# 516_outin_arduino.net
KiCad netlist of a schematic drawn in EAGLE
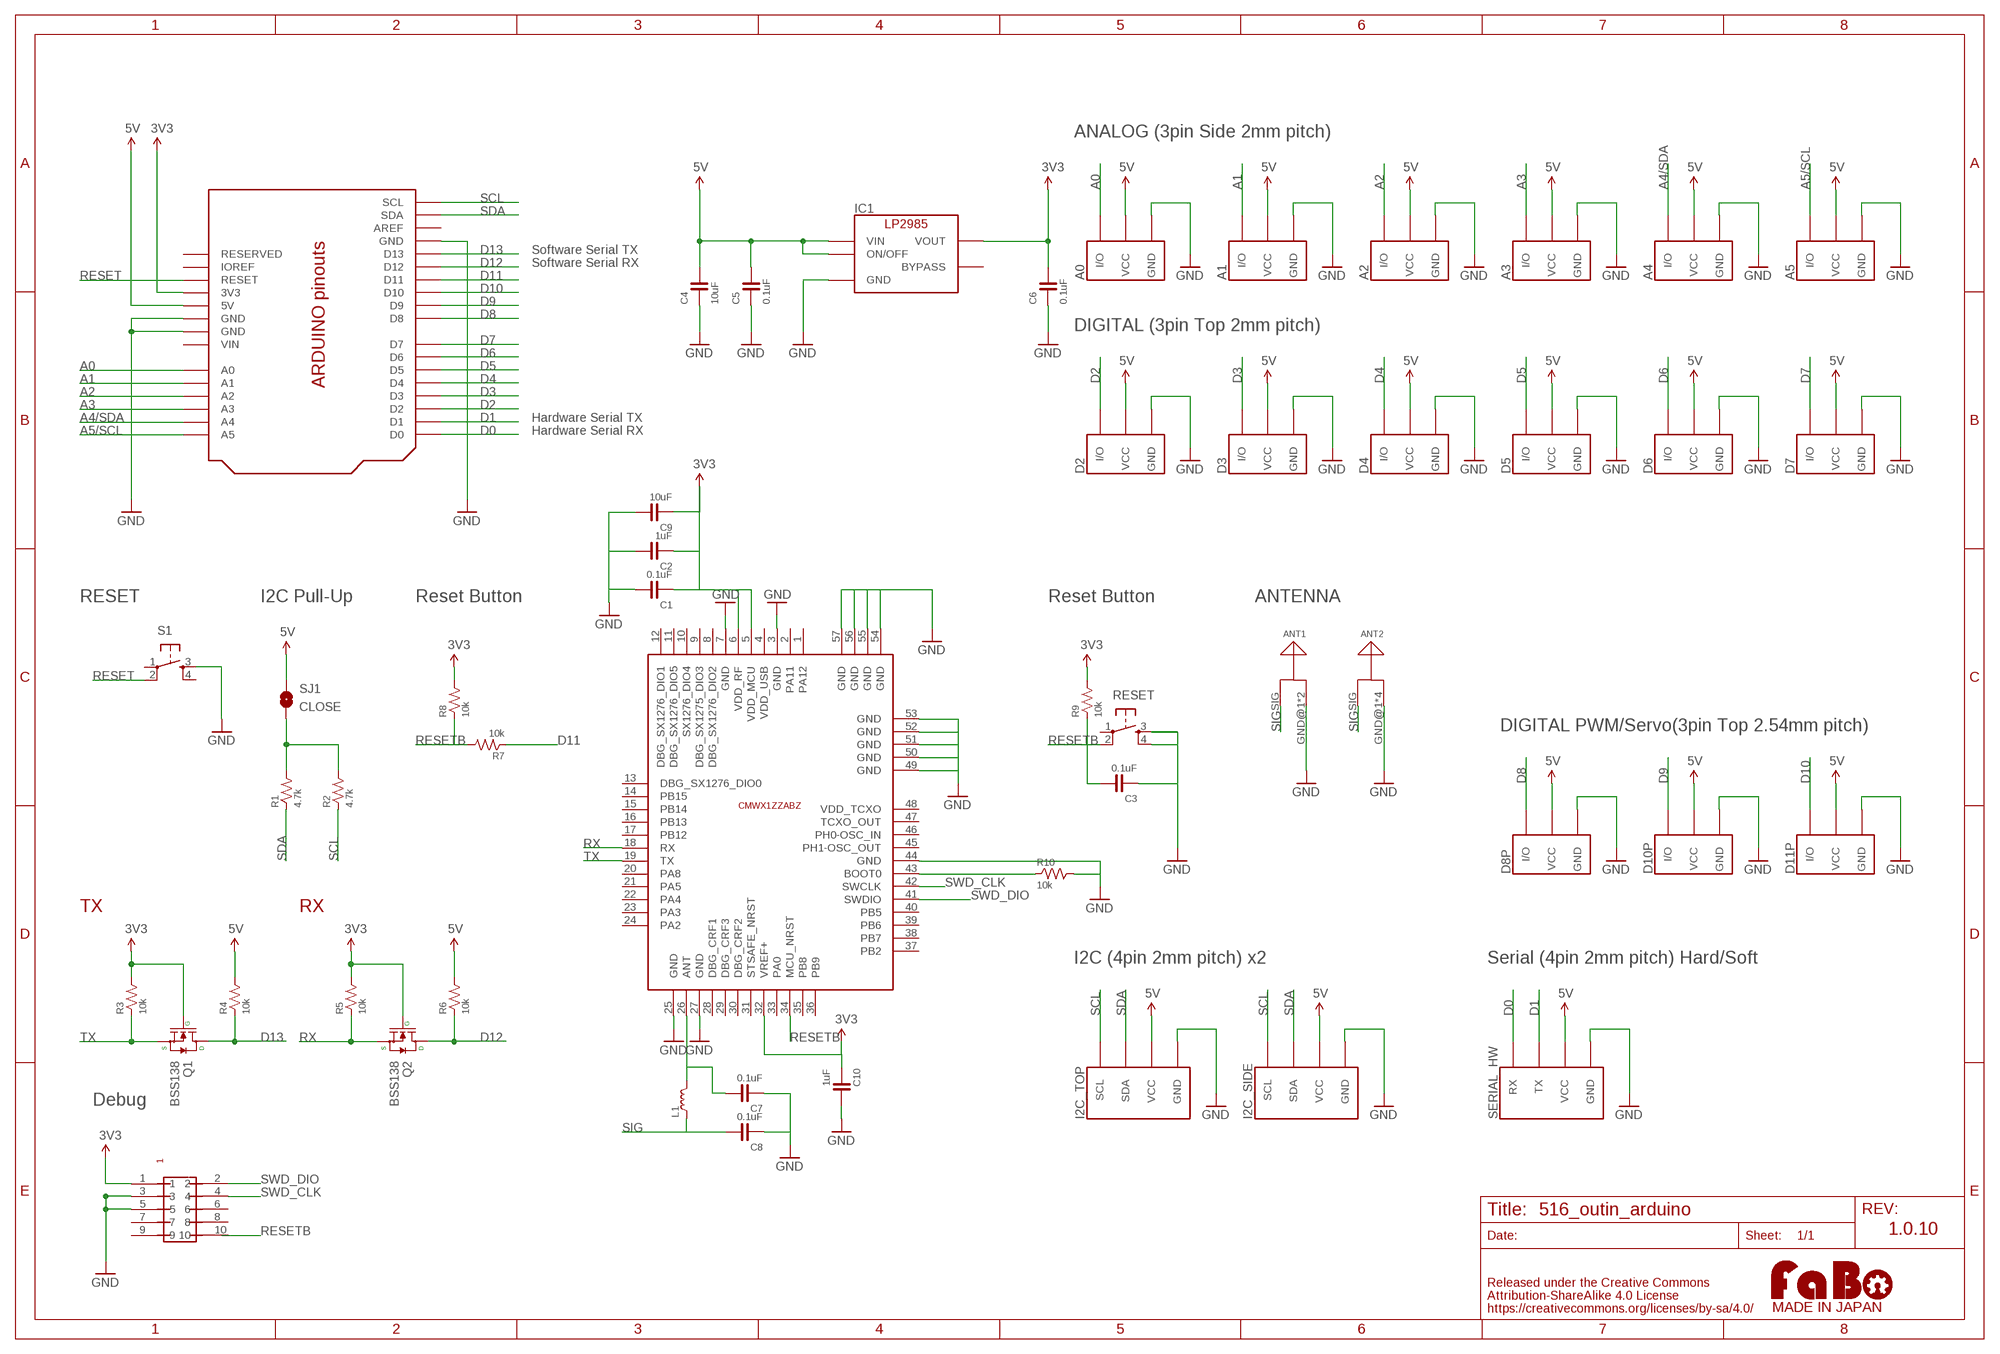
[diagram p0: schematic, sheet 1]

(export (version "E")
  (design (tool "Eeschema 10.0.6"))
  (components
    (comp (ref "A0")
      (value "FABO_BRICK_3PIN-S03B-PASK-2_LONG")
      (footprint "eagle-import:FABO_BRICK_3PIN_S03B-PASK-2_LONG")
      (libsource (lib "eagle-import") (part "FABO_BRICK_3PIN-S03B-PASK-2_LONG"))
    )
    (comp (ref "A1")
      (value "FABO_BRICK_3PIN-S03B-PASK-2_LONG")
      (footprint "eagle-import:FABO_BRICK_3PIN_S03B-PASK-2_LONG")
      (libsource (lib "eagle-import") (part "FABO_BRICK_3PIN-S03B-PASK-2_LONG"))
    )
    (comp (ref "A2")
      (value "FABO_BRICK_3PIN-S03B-PASK-2_LONG")
      (footprint "eagle-import:FABO_BRICK_3PIN_S03B-PASK-2_LONG")
      (libsource (lib "eagle-import") (part "FABO_BRICK_3PIN-S03B-PASK-2_LONG"))
    )
    (comp (ref "A3")
      (value "FABO_BRICK_3PIN-S03B-PASK-2_LONG")
      (footprint "eagle-import:FABO_BRICK_3PIN_S03B-PASK-2_LONG")
      (libsource (lib "eagle-import") (part "FABO_BRICK_3PIN-S03B-PASK-2_LONG"))
    )
    (comp (ref "A4")
      (value "FABO_BRICK_3PIN-S03B-PASK-2_LONG")
      (footprint "eagle-import:FABO_BRICK_3PIN_S03B-PASK-2_LONG")
      (libsource (lib "eagle-import") (part "FABO_BRICK_3PIN-S03B-PASK-2_LONG"))
    )
    (comp (ref "A5")
      (value "FABO_BRICK_3PIN-S03B-PASK-2_LONG")
      (footprint "eagle-import:FABO_BRICK_3PIN_S03B-PASK-2_LONG")
      (libsource (lib "eagle-import") (part "FABO_BRICK_3PIN-S03B-PASK-2_LONG"))
    )
    (comp (ref "ANT1")
      (value "ANTENA_HIROSE-UF-L")
      (footprint "eagle-import:HIROSE-UF-L")
      (libsource (lib "eagle-import") (part "ANTENA_HIROSE-UF-L"))
    )
    (comp (ref "ANT2")
      (value "ANTENA_SMA-J-P-H-RA-TH1")
      (footprint "eagle-import:SMA–J–P–H–RA–TH1")
      (libsource (lib "eagle-import") (part "ANTENA_SMA-J-P-H-RA-TH1"))
    )
    (comp (ref "C1")
      (value "0.1uF")
      (footprint "eagle-import:0603-NARROW")
      (libsource (lib "eagle-import") (part "CAPACITOR-0603_NARROW"))
    )
    (comp (ref "C2")
      (value "1uF")
      (footprint "eagle-import:0603-NARROW")
      (libsource (lib "eagle-import") (part "CAPACITOR-0603_NARROW"))
    )
    (comp (ref "C3")
      (value "0.1uF")
      (footprint "eagle-import:0603-NARROW")
      (libsource (lib "eagle-import") (part "CAPACITOR-0603_NARROW"))
    )
    (comp (ref "C4")
      (value "10uF")
      (footprint "eagle-import:0603-NARROW")
      (libsource (lib "eagle-import") (part "CAPACITOR-0603_NARROW"))
    )
    (comp (ref "C5")
      (value "0.1uF")
      (footprint "eagle-import:0603-NARROW")
      (libsource (lib "eagle-import") (part "CAPACITOR-0603_NARROW"))
    )
    (comp (ref "C6")
      (value "0.1uF")
      (footprint "eagle-import:0603-NARROW")
      (libsource (lib "eagle-import") (part "CAPACITOR-0603_NARROW"))
    )
    (comp (ref "C7")
      (value "0.1uF")
      (footprint "eagle-import:0603-NARROW")
      (libsource (lib "eagle-import") (part "CAPACITOR-0603_NARROW"))
    )
    (comp (ref "C8")
      (value "0.1uF")
      (footprint "eagle-import:0603-NARROW")
      (libsource (lib "eagle-import") (part "CAPACITOR-0603_NARROW"))
    )
    (comp (ref "C9")
      (value "10uF")
      (footprint "eagle-import:0603-NARROW")
      (libsource (lib "eagle-import") (part "CAPACITOR-0603_NARROW"))
    )
    (comp (ref "C10")
      (value "1uF")
      (footprint "eagle-import:0603-NARROW")
      (libsource (lib "eagle-import") (part "CAPACITOR-0603_NARROW"))
    )
    (comp (ref "D2")
      (value "FABO_BRICK_3PIN-B03B-PASK-1")
      (footprint "eagle-import:FABO_BRICK_3PIN_B03B-PASK-1")
      (libsource (lib "eagle-import") (part "FABO_BRICK_3PIN-B03B-PASK-1"))
    )
    (comp (ref "D3")
      (value "FABO_BRICK_3PIN-B03B-PASK-1")
      (footprint "eagle-import:FABO_BRICK_3PIN_B03B-PASK-1")
      (libsource (lib "eagle-import") (part "FABO_BRICK_3PIN-B03B-PASK-1"))
    )
    (comp (ref "D4")
      (value "FABO_BRICK_3PIN-B03B-PASK-1")
      (footprint "eagle-import:FABO_BRICK_3PIN_B03B-PASK-1")
      (libsource (lib "eagle-import") (part "FABO_BRICK_3PIN-B03B-PASK-1"))
    )
    (comp (ref "D5")
      (value "FABO_BRICK_3PIN-B03B-PASK-1")
      (footprint "eagle-import:FABO_BRICK_3PIN_B03B-PASK-1")
      (libsource (lib "eagle-import") (part "FABO_BRICK_3PIN-B03B-PASK-1"))
    )
    (comp (ref "D6")
      (value "FABO_BRICK_3PIN-B03B-PASK-1")
      (footprint "eagle-import:FABO_BRICK_3PIN_B03B-PASK-1")
      (libsource (lib "eagle-import") (part "FABO_BRICK_3PIN-B03B-PASK-1"))
    )
    (comp (ref "D7")
      (value "FABO_BRICK_3PIN-B03B-PASK-1")
      (footprint "eagle-import:FABO_BRICK_3PIN_B03B-PASK-1")
      (libsource (lib "eagle-import") (part "FABO_BRICK_3PIN-B03B-PASK-1"))
    )
    (comp (ref "D8P")
      (value "FABO_BRICK_3PIN-HEADER")
      (footprint "eagle-import:FABO_BRICK_3PIN_HEADER")
      (libsource (lib "eagle-import") (part "FABO_BRICK_3PIN-HEADER"))
    )
    (comp (ref "D10P")
      (value "FABO_BRICK_3PIN-HEADER")
      (footprint "eagle-import:FABO_BRICK_3PIN_HEADER")
      (libsource (lib "eagle-import") (part "FABO_BRICK_3PIN-HEADER"))
    )
    (comp (ref "D11P")
      (value "FABO_BRICK_3PIN-HEADER")
      (footprint "eagle-import:FABO_BRICK_3PIN_HEADER")
      (libsource (lib "eagle-import") (part "FABO_BRICK_3PIN-HEADER"))
    )
    (comp (ref "I2C_SIDE")
      (value "FABO_BRICK_I2C-S04B-PASK-2_LONG")
      (footprint "eagle-import:FABO_BRICK_I2C_S04B-PASK-2_LONG")
      (libsource (lib "eagle-import") (part "FABO_BRICK_I2C-S04B-PASK-2_LONG"))
    )
    (comp (ref "I2C_TOP")
      (value "FABO_BRICK_I2C-B04B-PASK-1")
      (footprint "eagle-import:FABO_BRICK_I2C_B04B-PASK-1")
      (libsource (lib "eagle-import") (part "FABO_BRICK_I2C-B04B-PASK-1"))
    )
    (comp (ref "IC1")
      (value "LP2985-33DBV")
      (footprint "eagle-import:SOT-23-5")
      (libsource (lib "eagle-import") (part "LP2985-33DBV"))
    )
    (comp (ref "L1")
      (value "COIL-0603")
      (footprint "eagle-import:0603")
      (libsource (lib "eagle-import") (part "COIL-0603"))
    )
    (comp (ref "Q1")
      (value "BSS138")
      (footprint "eagle-import:SOT23-3")
      (libsource (lib "eagle-import") (part "MOSFET-N"))
    )
    (comp (ref "Q2")
      (value "BSS138")
      (footprint "eagle-import:SOT23-3")
      (libsource (lib "eagle-import") (part "MOSFET-N"))
    )
    (comp (ref "R1")
      (value "4.7k")
      (footprint "eagle-import:0603")
      (libsource (lib "eagle-import") (part "RESISTOR-0603"))
    )
    (comp (ref "R2")
      (value "4.7k")
      (footprint "eagle-import:0603")
      (libsource (lib "eagle-import") (part "RESISTOR-0603"))
    )
    (comp (ref "R3")
      (value "10k")
      (footprint "eagle-import:0603-NARROW")
      (libsource (lib "eagle-import") (part "RESISTOR-0603-NARROW"))
    )
    (comp (ref "R4")
      (value "10k")
      (footprint "eagle-import:0603-NARROW")
      (libsource (lib "eagle-import") (part "RESISTOR-0603-NARROW"))
    )
    (comp (ref "R5")
      (value "10k")
      (footprint "eagle-import:0603-NARROW")
      (libsource (lib "eagle-import") (part "RESISTOR-0603-NARROW"))
    )
    (comp (ref "R6")
      (value "10k")
      (footprint "eagle-import:0603-NARROW")
      (libsource (lib "eagle-import") (part "RESISTOR-0603-NARROW"))
    )
    (comp (ref "R7")
      (value "10k")
      (footprint "eagle-import:0603-NARROW")
      (libsource (lib "eagle-import") (part "RESISTOR-0603-NARROW"))
    )
    (comp (ref "R8")
      (value "10k")
      (footprint "eagle-import:0603-NARROW")
      (libsource (lib "eagle-import") (part "RESISTOR-0603-NARROW"))
    )
    (comp (ref "R9")
      (value "10k")
      (footprint "eagle-import:0603-NARROW")
      (libsource (lib "eagle-import") (part "RESISTOR-0603-NARROW"))
    )
    (comp (ref "R10")
      (value "10k")
      (footprint "eagle-import:0603-NARROW")
      (libsource (lib "eagle-import") (part "RESISTOR-0603-NARROW"))
    )
    (comp (ref "RESET")
      (value "TACT-SWITCH-SMD_KMR2")
      (footprint "eagle-import:KMR2")
      (libsource (lib "eagle-import") (part "TACT-SWITCH-SMD_KMR2"))
    )
    (comp (ref "S1")
      (value "TACT-SWITCH-6MM")
      (footprint "eagle-import:DTS_6_V")
      (libsource (lib "eagle-import") (part "TACT-SWITCH-6MM"))
    )
    (comp (ref "SERIAL_HW")
      (value "FABO_BRICK_SERIAL-B04B-PASK-1")
      (footprint "eagle-import:FABO_BRICK_SERIAL_B04B-PASK-1")
      (libsource (lib "eagle-import") (part "FABO_BRICK_SERIAL-B04B-PASK-1"))
    )
    (comp (ref "SJ1")
      (value "CLOSE")
      (footprint "eagle-import:SMD-JUMPER-2-CLOSE")
      (libsource (lib "eagle-import") (part "SMD-JUMPER-2-CLOSE"))
    )
    (comp (ref "U$3")
      (value "CMWX1ZZABZ")
      (footprint "eagle-import:CMWX1ZZABZ")
      (libsource (lib "eagle-import") (part "CMWX1ZZABZ"))
    )
    (comp (ref "U$10")
      (value "LOGO_FABO-M")
      (footprint "eagle-import:LOGO_FABO_MS")
      (libsource (lib "eagle-import") (part "LOGO_FABO-M"))
    )
    (comp (ref "U$15")
      (value "PIN-HEADER-SMT(1.27MM)2X5")
      (footprint "eagle-import:PIN-HEADER-SMT(1.27MM)2X5")
      (libsource (lib "eagle-import") (part "PIN-HEADER-SMT(1.27MM)2X5"))
    )
    (comp (ref "U1")
      (value "ARDUINO_UNO_R3_SHIELD-OUTIN")
      (footprint "eagle-import:ARDUINO_SHIELD_OUTIN")
      (libsource (lib "eagle-import") (part "ARDUINO_UNO_R3_SHIELD-OUTIN"))
    )
  )
  (nets
    (net (code "1") (name "/A0") (class "Default")
      (node (ref "A0") (pin "I/O") (pinfunction "I/O_I/O") (pintype "bidirectional"))
      (node (ref "U1") (pin "A0") (pinfunction "A0_A0") (pintype "bidirectional"))
    )
    (net (code "2") (name "/A1") (class "Default")
      (node (ref "A1") (pin "I/O") (pinfunction "I/O_I/O") (pintype "bidirectional"))
      (node (ref "U1") (pin "A1") (pinfunction "A1_A1") (pintype "bidirectional"))
    )
    (net (code "3") (name "/A2") (class "Default")
      (node (ref "A2") (pin "I/O") (pinfunction "I/O_I/O") (pintype "bidirectional"))
      (node (ref "U1") (pin "A2") (pinfunction "A2_A2") (pintype "bidirectional"))
    )
    (net (code "4") (name "/A3") (class "Default")
      (node (ref "A3") (pin "I/O") (pinfunction "I/O_I/O") (pintype "bidirectional"))
      (node (ref "U1") (pin "A3") (pinfunction "A3_A3") (pintype "bidirectional"))
    )
    (net (code "5") (name "/A4{slash}SDA") (class "Default")
      (node (ref "A4") (pin "I/O") (pinfunction "I/O_I/O") (pintype "bidirectional"))
      (node (ref "U1") (pin "A4") (pinfunction "A4_A4") (pintype "bidirectional"))
    )
    (net (code "6") (name "/A5{slash}SCL") (class "Default")
      (node (ref "A5") (pin "I/O") (pinfunction "I/O_I/O") (pintype "bidirectional"))
      (node (ref "U1") (pin "A5") (pinfunction "A5_A5") (pintype "bidirectional"))
    )
    (net (code "7") (name "/D0") (class "Default")
      (node (ref "SERIAL_HW") (pin "RX") (pinfunction "RX_RX") (pintype "bidirectional"))
      (node (ref "U1") (pin "D0") (pinfunction "D0_D0") (pintype "bidirectional"))
    )
    (net (code "8") (name "/D1") (class "Default")
      (node (ref "SERIAL_HW") (pin "TX") (pinfunction "TX_TX") (pintype "bidirectional"))
      (node (ref "U1") (pin "D1") (pinfunction "D1_D1") (pintype "bidirectional"))
    )
    (net (code "9") (name "/D2") (class "Default")
      (node (ref "D2") (pin "I/O") (pinfunction "I/O_I/O") (pintype "bidirectional"))
      (node (ref "U1") (pin "D2") (pinfunction "D2_D2") (pintype "bidirectional"))
    )
    (net (code "10") (name "/D3") (class "Default")
      (node (ref "D3") (pin "I/O") (pinfunction "I/O_I/O") (pintype "bidirectional"))
      (node (ref "U1") (pin "D3") (pinfunction "D3_D3") (pintype "bidirectional"))
    )
    (net (code "11") (name "/D4") (class "Default")
      (node (ref "D4") (pin "I/O") (pinfunction "I/O_I/O") (pintype "bidirectional"))
      (node (ref "U1") (pin "D4") (pinfunction "D4_D4") (pintype "bidirectional"))
    )
    (net (code "12") (name "/D5") (class "Default")
      (node (ref "D5") (pin "I/O") (pinfunction "I/O_I/O") (pintype "bidirectional"))
      (node (ref "U1") (pin "D5") (pinfunction "D5_D5") (pintype "bidirectional"))
    )
    (net (code "13") (name "/D6") (class "Default")
      (node (ref "D6") (pin "I/O") (pinfunction "I/O_I/O") (pintype "bidirectional"))
      (node (ref "U1") (pin "D6") (pinfunction "D6_D6") (pintype "bidirectional"))
    )
    (net (code "14") (name "/D7") (class "Default")
      (node (ref "D7") (pin "I/O") (pinfunction "I/O_I/O") (pintype "bidirectional"))
      (node (ref "U1") (pin "D7") (pinfunction "D7_D7") (pintype "bidirectional"))
    )
    (net (code "15") (name "/D8") (class "Default")
      (node (ref "D8P") (pin "I/O") (pinfunction "I/O_I/O") (pintype "bidirectional"))
      (node (ref "U1") (pin "D8") (pinfunction "D8_D8") (pintype "bidirectional"))
    )
    (net (code "16") (name "/D9") (class "Default")
      (node (ref "D10P") (pin "I/O") (pinfunction "I/O_I/O") (pintype "bidirectional"))
      (node (ref "U1") (pin "D9") (pinfunction "D9_D9") (pintype "bidirectional"))
    )
    (net (code "17") (name "/D10") (class "Default")
      (node (ref "D11P") (pin "I/O") (pinfunction "I/O_I/O") (pintype "bidirectional"))
      (node (ref "U1") (pin "D10") (pinfunction "D10_D10") (pintype "bidirectional"))
    )
    (net (code "18") (name "/D11") (class "Default")
      (node (ref "R7") (pin "1") (pinfunction "1_1") (pintype "bidirectional"))
      (node (ref "U1") (pin "D11") (pinfunction "D11_D11") (pintype "bidirectional"))
    )
    (net (code "19") (name "/D12") (class "Default")
      (node (ref "Q2") (pin "3") (pinfunction "D_3") (pintype "passive"))
      (node (ref "R6") (pin "1") (pinfunction "1_1") (pintype "bidirectional"))
      (node (ref "U1") (pin "D12") (pinfunction "D12_D12") (pintype "bidirectional"))
    )
    (net (code "20") (name "/D13") (class "Default")
      (node (ref "Q1") (pin "3") (pinfunction "D_3") (pintype "passive"))
      (node (ref "R4") (pin "1") (pinfunction "1_1") (pintype "bidirectional"))
      (node (ref "U1") (pin "D13") (pinfunction "D13_D13") (pintype "bidirectional"))
    )
    (net (code "21") (name "/RESET") (class "Default")
      (node (ref "S1") (pin "2") (pinfunction "2_2") (pintype "passive"))
      (node (ref "U1") (pin "RESET") (pinfunction "RESET_RESET") (pintype "bidirectional"))
    )
    (net (code "22") (name "/RESETB") (class "Default")
      (node (ref "C3") (pin "2") (pinfunction "2_2") (pintype "passive"))
      (node (ref "R7") (pin "2") (pinfunction "2_2") (pintype "bidirectional"))
      (node (ref "R8") (pin "1") (pinfunction "1_1") (pintype "bidirectional"))
      (node (ref "R9") (pin "1") (pinfunction "1_1") (pintype "bidirectional"))
      (node (ref "RESET") (pin "2") (pinfunction "2_2") (pintype "passive"))
      (node (ref "U$15") (pin "10") (pinfunction "10_10") (pintype "bidirectional"))
      (node (ref "U$3") (pin "34") (pinfunction "MCU_NRST_34") (pintype "bidirectional"))
    )
    (net (code "23") (name "/RX") (class "Default")
      (node (ref "Q2") (pin "2") (pinfunction "S_2") (pintype "passive"))
      (node (ref "R5") (pin "1") (pinfunction "1_1") (pintype "bidirectional"))
      (node (ref "U$3") (pin "18") (pinfunction "RX_18") (pintype "bidirectional"))
    )
    (net (code "24") (name "/SCL") (class "Default")
      (node (ref "I2C_SIDE") (pin "SCL") (pinfunction "SCL_SCL") (pintype "bidirectional"))
      (node (ref "I2C_TOP") (pin "SCL") (pinfunction "SCL_SCL") (pintype "bidirectional"))
      (node (ref "R2") (pin "1") (pinfunction "1_1") (pintype "bidirectional"))
      (node (ref "U1") (pin "SCL") (pinfunction "SCL_SCL") (pintype "bidirectional"))
    )
    (net (code "25") (name "/SDA") (class "Default")
      (node (ref "I2C_SIDE") (pin "SDA") (pinfunction "SDA_SDA") (pintype "bidirectional"))
      (node (ref "I2C_TOP") (pin "SDA") (pinfunction "SDA_SDA") (pintype "bidirectional"))
      (node (ref "R1") (pin "1") (pinfunction "1_1") (pintype "bidirectional"))
      (node (ref "U1") (pin "SDA") (pinfunction "SDA_SDA") (pintype "bidirectional"))
    )
    (net (code "26") (name "/SIG") (class "Default")
      (node (ref "ANT1") (pin "SIG") (pinfunction "SIG_SIG") (pintype "passive"))
      (node (ref "ANT2") (pin "SIG") (pinfunction "SIG_SIG") (pintype "passive"))
      (node (ref "C8") (pin "2") (pinfunction "2_2") (pintype "passive"))
      (node (ref "L1") (pin "1") (pinfunction "1_1") (pintype "bidirectional"))
    )
    (net (code "27") (name "/SWD_CLK") (class "Default")
      (node (ref "U$15") (pin "4") (pinfunction "4_4") (pintype "bidirectional"))
      (node (ref "U$3") (pin "42") (pinfunction "SWCLK_42") (pintype "bidirectional"))
    )
    (net (code "28") (name "/SWD_DIO") (class "Default")
      (node (ref "U$15") (pin "2") (pinfunction "2_2") (pintype "bidirectional"))
      (node (ref "U$3") (pin "41") (pinfunction "SWDIO_41") (pintype "bidirectional"))
    )
    (net (code "29") (name "/TX") (class "Default")
      (node (ref "Q1") (pin "2") (pinfunction "S_2") (pintype "passive"))
      (node (ref "R3") (pin "1") (pinfunction "1_1") (pintype "bidirectional"))
      (node (ref "U$3") (pin "19") (pinfunction "TX_19") (pintype "bidirectional"))
    )
    (net (code "30") (name "/VIN") (class "Default")
      (node (ref "U1") (pin "VIN") (pinfunction "VIN_VIN") (pintype "power_in"))
    )
    (net (code "31") (name "3V3") (class "Default")
      (node (ref "C1") (pin "1") (pinfunction "1_1") (pintype "passive"))
      (node (ref "C10") (pin "1") (pinfunction "1_1") (pintype "passive"))
      (node (ref "C2") (pin "1") (pinfunction "1_1") (pintype "passive"))
      (node (ref "C6") (pin "2") (pinfunction "2_2") (pintype "passive"))
      (node (ref "C9") (pin "1") (pinfunction "1_1") (pintype "passive"))
      (node (ref "IC1") (pin "5") (pinfunction "VOUT_5") (pintype "output"))
      (node (ref "Q1") (pin "1") (pinfunction "G_1") (pintype "passive"))
      (node (ref "Q2") (pin "1") (pinfunction "G_1") (pintype "passive"))
      (node (ref "R3") (pin "2") (pinfunction "2_2") (pintype "bidirectional"))
      (node (ref "R5") (pin "2") (pinfunction "2_2") (pintype "bidirectional"))
      (node (ref "R8") (pin "2") (pinfunction "2_2") (pintype "bidirectional"))
      (node (ref "R9") (pin "2") (pinfunction "2_2") (pintype "bidirectional"))
      (node (ref "U$15") (pin "1") (pinfunction "1_1") (pintype "bidirectional"))
      (node (ref "U$3") (pin "32") (pinfunction "VREF+_32") (pintype "bidirectional"))
      (node (ref "U$3") (pin "5") (pinfunction "VDD_MCU_5") (pintype "bidirectional"))
      (node (ref "U$3") (pin "6") (pinfunction "VDD_RF_6") (pintype "bidirectional"))
      (node (ref "U1") (pin "3V3") (pinfunction "3V3_3V3") (pintype "power_in"))
    )
    (net (code "32") (name "5V") (class "Default")
      (node (ref "A0") (pin "VCC") (pinfunction "VCC_VCC") (pintype "bidirectional"))
      (node (ref "A1") (pin "VCC") (pinfunction "VCC_VCC") (pintype "bidirectional"))
      (node (ref "A2") (pin "VCC") (pinfunction "VCC_VCC") (pintype "bidirectional"))
      (node (ref "A3") (pin "VCC") (pinfunction "VCC_VCC") (pintype "bidirectional"))
      (node (ref "A4") (pin "VCC") (pinfunction "VCC_VCC") (pintype "bidirectional"))
      (node (ref "A5") (pin "VCC") (pinfunction "VCC_VCC") (pintype "bidirectional"))
      (node (ref "C4") (pin "2") (pinfunction "2_2") (pintype "passive"))
      (node (ref "C5") (pin "2") (pinfunction "2_2") (pintype "passive"))
      (node (ref "D10P") (pin "VCC") (pinfunction "VCC_VCC") (pintype "bidirectional"))
      (node (ref "D11P") (pin "VCC") (pinfunction "VCC_VCC") (pintype "bidirectional"))
      (node (ref "D2") (pin "VCC") (pinfunction "VCC_VCC") (pintype "bidirectional"))
      (node (ref "D3") (pin "VCC") (pinfunction "VCC_VCC") (pintype "bidirectional"))
      (node (ref "D4") (pin "VCC") (pinfunction "VCC_VCC") (pintype "bidirectional"))
      (node (ref "D5") (pin "VCC") (pinfunction "VCC_VCC") (pintype "bidirectional"))
      (node (ref "D6") (pin "VCC") (pinfunction "VCC_VCC") (pintype "bidirectional"))
      (node (ref "D7") (pin "VCC") (pinfunction "VCC_VCC") (pintype "bidirectional"))
      (node (ref "D8P") (pin "VCC") (pinfunction "VCC_VCC") (pintype "bidirectional"))
      (node (ref "I2C_SIDE") (pin "VCC") (pinfunction "VCC_VCC") (pintype "bidirectional"))
      (node (ref "I2C_TOP") (pin "VCC") (pinfunction "VCC_VCC") (pintype "bidirectional"))
      (node (ref "IC1") (pin "1") (pinfunction "VIN_1") (pintype "input"))
      (node (ref "IC1") (pin "3") (pinfunction "ON/OFF_3") (pintype "input"))
      (node (ref "R4") (pin "2") (pinfunction "2_2") (pintype "bidirectional"))
      (node (ref "R6") (pin "2") (pinfunction "2_2") (pintype "bidirectional"))
      (node (ref "SERIAL_HW") (pin "VCC") (pinfunction "VCC_VCC") (pintype "bidirectional"))
      (node (ref "SJ1") (pin "1") (pinfunction "1_1") (pintype "passive"))
      (node (ref "U1") (pin "5V") (pinfunction "5V_5V") (pintype "power_in"))
    )
    (net (code "33") (name "GND") (class "Default")
      (node (ref "A0") (pin "GND") (pinfunction "GND_GND") (pintype "bidirectional"))
      (node (ref "A1") (pin "GND") (pinfunction "GND_GND") (pintype "bidirectional"))
      (node (ref "A2") (pin "GND") (pinfunction "GND_GND") (pintype "bidirectional"))
      (node (ref "A3") (pin "GND") (pinfunction "GND_GND") (pintype "bidirectional"))
      (node (ref "A4") (pin "GND") (pinfunction "GND_GND") (pintype "bidirectional"))
      (node (ref "A5") (pin "GND") (pinfunction "GND_GND") (pintype "bidirectional"))
      (node (ref "ANT1") (pin "GND@1") (pinfunction "GND_GND@1") (pintype "passive"))
      (node (ref "ANT1") (pin "GND@2") (pinfunction "GND_GND@2") (pintype "passive"))
      (node (ref "ANT2") (pin "GND@1") (pinfunction "GND_GND@1") (pintype "passive"))
      (node (ref "ANT2") (pin "GND@2") (pinfunction "GND_GND@2") (pintype "passive"))
      (node (ref "ANT2") (pin "GND@3") (pinfunction "GND_GND@3") (pintype "passive"))
      (node (ref "ANT2") (pin "GND@4") (pinfunction "GND_GND@4") (pintype "passive"))
      (node (ref "C1") (pin "2") (pinfunction "2_2") (pintype "passive"))
      (node (ref "C10") (pin "2") (pinfunction "2_2") (pintype "passive"))
      (node (ref "C2") (pin "2") (pinfunction "2_2") (pintype "passive"))
      (node (ref "C3") (pin "1") (pinfunction "1_1") (pintype "passive"))
      (node (ref "C4") (pin "1") (pinfunction "1_1") (pintype "passive"))
      (node (ref "C5") (pin "1") (pinfunction "1_1") (pintype "passive"))
      (node (ref "C6") (pin "1") (pinfunction "1_1") (pintype "passive"))
      (node (ref "C7") (pin "1") (pinfunction "1_1") (pintype "passive"))
      (node (ref "C8") (pin "1") (pinfunction "1_1") (pintype "passive"))
      (node (ref "C9") (pin "2") (pinfunction "2_2") (pintype "passive"))
      (node (ref "D10P") (pin "GND") (pinfunction "GND_GND") (pintype "bidirectional"))
      (node (ref "D11P") (pin "GND") (pinfunction "GND_GND") (pintype "bidirectional"))
      (node (ref "D2") (pin "GND") (pinfunction "GND_GND") (pintype "bidirectional"))
      (node (ref "D3") (pin "GND") (pinfunction "GND_GND") (pintype "bidirectional"))
      (node (ref "D4") (pin "GND") (pinfunction "GND_GND") (pintype "bidirectional"))
      (node (ref "D5") (pin "GND") (pinfunction "GND_GND") (pintype "bidirectional"))
      (node (ref "D6") (pin "GND") (pinfunction "GND_GND") (pintype "bidirectional"))
      (node (ref "D7") (pin "GND") (pinfunction "GND_GND") (pintype "bidirectional"))
      (node (ref "D8P") (pin "GND") (pinfunction "GND_GND") (pintype "bidirectional"))
      (node (ref "I2C_SIDE") (pin "GND") (pinfunction "GND_GND") (pintype "bidirectional"))
      (node (ref "I2C_TOP") (pin "GND") (pinfunction "GND_GND") (pintype "bidirectional"))
      (node (ref "IC1") (pin "2") (pinfunction "GND_2") (pintype "power_in"))
      (node (ref "R10") (pin "2") (pinfunction "2_2") (pintype "bidirectional"))
      (node (ref "RESET") (pin "3") (pinfunction "3_3") (pintype "passive"))
      (node (ref "RESET") (pin "4") (pinfunction "4_4") (pintype "passive"))
      (node (ref "S1") (pin "3") (pinfunction "3_3") (pintype "passive"))
      (node (ref "SERIAL_HW") (pin "GND") (pinfunction "GND_GND") (pintype "bidirectional"))
      (node (ref "U$15") (pin "3") (pinfunction "3_3") (pintype "bidirectional"))
      (node (ref "U$15") (pin "5") (pinfunction "5_5") (pintype "bidirectional"))
      (node (ref "U$3") (pin "25") (pinfunction "GND_25") (pintype "bidirectional"))
      (node (ref "U$3") (pin "27") (pinfunction "GND_27") (pintype "bidirectional"))
      (node (ref "U$3") (pin "3") (pinfunction "GND_3") (pintype "bidirectional"))
      (node (ref "U$3") (pin "44") (pinfunction "GND_44") (pintype "bidirectional"))
      (node (ref "U$3") (pin "49") (pinfunction "GND_49") (pintype "bidirectional"))
      (node (ref "U$3") (pin "50") (pinfunction "GND_50") (pintype "bidirectional"))
      (node (ref "U$3") (pin "51") (pinfunction "GND_51") (pintype "bidirectional"))
      (node (ref "U$3") (pin "52") (pinfunction "GND_52") (pintype "bidirectional"))
      (node (ref "U$3") (pin "53") (pinfunction "GND_53") (pintype "bidirectional"))
      (node (ref "U$3") (pin "54") (pinfunction "GND_54") (pintype "bidirectional"))
      (node (ref "U$3") (pin "55") (pinfunction "GND_55") (pintype "bidirectional"))
      (node (ref "U$3") (pin "56") (pinfunction "GND_56") (pintype "bidirectional"))
      (node (ref "U$3") (pin "57") (pinfunction "GND_57") (pintype "bidirectional"))
      (node (ref "U$3") (pin "7") (pinfunction "GND_7") (pintype "bidirectional"))
      (node (ref "U1") (pin "GND1") (pinfunction "GND_GND1") (pintype "power_in"))
      (node (ref "U1") (pin "GND2") (pinfunction "GND_GND2") (pintype "power_in"))
      (node (ref "U1") (pin "GND3") (pinfunction "GND_GND3") (pintype "power_in"))
    )
    (net (code "34") (name "Net-(R1-Pad2)") (class "Default")
      (node (ref "R1") (pin "2") (pinfunction "2_2") (pintype "bidirectional"))
      (node (ref "R2") (pin "2") (pinfunction "2_2") (pintype "bidirectional"))
      (node (ref "SJ1") (pin "2") (pinfunction "2_2") (pintype "passive"))
    )
    (net (code "35") (name "Net-(U$3-ANT)") (class "Default")
      (node (ref "C7") (pin "2") (pinfunction "2_2") (pintype "passive"))
      (node (ref "L1") (pin "2") (pinfunction "2_2") (pintype "bidirectional"))
      (node (ref "U$3") (pin "26") (pinfunction "ANT_26") (pintype "bidirectional"))
    )
    (net (code "36") (name "Net-(U$3-BOOT0)") (class "Default")
      (node (ref "R10") (pin "1") (pinfunction "1_1") (pintype "bidirectional"))
      (node (ref "U$3") (pin "43") (pinfunction "BOOT0_43") (pintype "bidirectional"))
    )
    (net (code "37") (name "unconnected-(IC1-BYPASS-Pad4)") (class "Default")
      (node (ref "IC1") (pin "4") (pinfunction "BYPASS_4") (pintype "bidirectional"))
    )
    (net (code "38") (name "unconnected-(RESET-Pad1)") (class "Default")
      (node (ref "RESET") (pin "1") (pinfunction "1_1") (pintype "passive"))
    )
    (net (code "39") (name "unconnected-(S1-Pad1)") (class "Default")
      (node (ref "S1") (pin "1") (pinfunction "1_1") (pintype "passive"))
    )
    (net (code "40") (name "unconnected-(S1-Pad4)") (class "Default")
      (node (ref "S1") (pin "4") (pinfunction "4_4") (pintype "passive"))
    )
    (net (code "41") (name "unconnected-(U$3-DBG_CRF1-Pad28)") (class "Default")
      (node (ref "U$3") (pin "28") (pinfunction "DBG_CRF1_28") (pintype "bidirectional"))
    )
    (net (code "42") (name "unconnected-(U$3-DBG_CRF2-Pad30)") (class "Default")
      (node (ref "U$3") (pin "30") (pinfunction "DBG_CRF2_30") (pintype "bidirectional"))
    )
    (net (code "43") (name "unconnected-(U$3-DBG_CRF3-Pad29)") (class "Default")
      (node (ref "U$3") (pin "29") (pinfunction "DBG_CRF3_29") (pintype "bidirectional"))
    )
    (net (code "44") (name "unconnected-(U$3-DBG_SX1275_DIO3-Pad9)") (class "Default")
      (node (ref "U$3") (pin "9") (pinfunction "DBG_SX1275_DIO3_9") (pintype "bidirectional"))
    )
    (net (code "45") (name "unconnected-(U$3-DBG_SX1276_DIO0-Pad13)") (class "Default")
      (node (ref "U$3") (pin "13") (pinfunction "DBG_SX1276_DIO0_13") (pintype "bidirectional"))
    )
    (net (code "46") (name "unconnected-(U$3-DBG_SX1276_DIO1-Pad12)") (class "Default")
      (node (ref "U$3") (pin "12") (pinfunction "DBG_SX1276_DIO1_12") (pintype "bidirectional"))
    )
    (net (code "47") (name "unconnected-(U$3-DBG_SX1276_DIO2-Pad8)") (class "Default")
      (node (ref "U$3") (pin "8") (pinfunction "DBG_SX1276_DIO2_8") (pintype "bidirectional"))
    )
    (net (code "48") (name "unconnected-(U$3-DBG_SX1276_DIO5-Pad11)") (class "Default")
      (node (ref "U$3") (pin "11") (pinfunction "DBG_SX1276_DIO5_11") (pintype "bidirectional"))
    )
    (net (code "49") (name "unconnected-(U$3-PA0-Pad33)") (class "Default")
      (node (ref "U$3") (pin "33") (pinfunction "PA0_33") (pintype "bidirectional"))
    )
    (net (code "50") (name "unconnected-(U$3-PA2-Pad24)") (class "Default")
      (node (ref "U$3") (pin "24") (pinfunction "PA2_24") (pintype "bidirectional"))
    )
    (net (code "51") (name "unconnected-(U$3-PA3-Pad23)") (class "Default")
      (node (ref "U$3") (pin "23") (pinfunction "PA3_23") (pintype "bidirectional"))
    )
    (net (code "52") (name "unconnected-(U$3-PA4-Pad22)") (class "Default")
      (node (ref "U$3") (pin "22") (pinfunction "PA4_22") (pintype "bidirectional"))
    )
    (net (code "53") (name "unconnected-(U$3-PA5-Pad21)") (class "Default")
      (node (ref "U$3") (pin "21") (pinfunction "PA5_21") (pintype "bidirectional"))
    )
    (net (code "54") (name "unconnected-(U$3-PA8-Pad20)") (class "Default")
      (node (ref "U$3") (pin "20") (pinfunction "PA8_20") (pintype "bidirectional"))
    )
    (net (code "55") (name "unconnected-(U$3-PA11-Pad2)") (class "Default")
      (node (ref "U$3") (pin "2") (pinfunction "PA11_2") (pintype "bidirectional"))
    )
    (net (code "56") (name "unconnected-(U$3-PA12-Pad1)") (class "Default")
      (node (ref "U$3") (pin "1") (pinfunction "PA12_1") (pintype "bidirectional"))
    )
    (net (code "57") (name "unconnected-(U$3-PB2-Pad37)") (class "Default")
      (node (ref "U$3") (pin "37") (pinfunction "PB2_37") (pintype "bidirectional"))
    )
    (net (code "58") (name "unconnected-(U$3-PB5-Pad40)") (class "Default")
      (node (ref "U$3") (pin "40") (pinfunction "PB5_40") (pintype "bidirectional"))
    )
    (net (code "59") (name "unconnected-(U$3-PB6-Pad39)") (class "Default")
      (node (ref "U$3") (pin "39") (pinfunction "PB6_39") (pintype "bidirectional"))
    )
    (net (code "60") (name "unconnected-(U$3-PB7-Pad38)") (class "Default")
      (node (ref "U$3") (pin "38") (pinfunction "PB7_38") (pintype "bidirectional"))
    )
    (net (code "61") (name "unconnected-(U$3-PB8-Pad35)") (class "Default")
      (node (ref "U$3") (pin "35") (pinfunction "PB8_35") (pintype "bidirectional"))
    )
    (net (code "62") (name "unconnected-(U$3-PB9-Pad36)") (class "Default")
      (node (ref "U$3") (pin "36") (pinfunction "PB9_36") (pintype "bidirectional"))
    )
    (net (code "63") (name "unconnected-(U$3-PB12-Pad17)") (class "Default")
      (node (ref "U$3") (pin "17") (pinfunction "PB12_17") (pintype "bidirectional"))
    )
    (net (code "64") (name "unconnected-(U$3-PB13-Pad16)") (class "Default")
      (node (ref "U$3") (pin "16") (pinfunction "PB13_16") (pintype "bidirectional"))
    )
    (net (code "65") (name "unconnected-(U$3-PB14-Pad15)") (class "Default")
      (node (ref "U$3") (pin "15") (pinfunction "PB14_15") (pintype "bidirectional"))
    )
    (net (code "66") (name "unconnected-(U$3-PB15-Pad14)") (class "Default")
      (node (ref "U$3") (pin "14") (pinfunction "PB15_14") (pintype "bidirectional"))
    )
    (net (code "67") (name "unconnected-(U$3-PH0-OSC_IN-Pad46)") (class "Default")
      (node (ref "U$3") (pin "46") (pinfunction "PH0-OSC_IN_46") (pintype "bidirectional"))
    )
    (net (code "68") (name "unconnected-(U$3-PH1-OSC_OUT-Pad45)") (class "Default")
      (node (ref "U$3") (pin "45") (pinfunction "PH1-OSC_OUT_45") (pintype "bidirectional"))
    )
    (net (code "69") (name "unconnected-(U$3-STSAFE_NRST-Pad31)") (class "Default")
      (node (ref "U$3") (pin "31") (pinfunction "STSAFE_NRST_31") (pintype "bidirectional"))
    )
    (net (code "70") (name "unconnected-(U$3-SX1276_DIO4-Pad10)") (class "Default")
      (node (ref "U$3") (pin "10") (pinfunction "SX1276_DIO4_10") (pintype "bidirectional"))
    )
    (net (code "71") (name "unconnected-(U$3-TCXO_OUT-Pad47)") (class "Default")
      (node (ref "U$3") (pin "47") (pinfunction "TCXO_OUT_47") (pintype "bidirectional"))
    )
    (net (code "72") (name "unconnected-(U$3-VDD_TCXO-Pad48)") (class "Default")
      (node (ref "U$3") (pin "48") (pinfunction "VDD_TCXO_48") (pintype "bidirectional"))
    )
    (net (code "73") (name "unconnected-(U$3-VDD_USB-Pad4)") (class "Default")
      (node (ref "U$3") (pin "4") (pinfunction "VDD_USB_4") (pintype "bidirectional"))
    )
    (net (code "74") (name "unconnected-(U$15-Pad6)") (class "Default")
      (node (ref "U$15") (pin "6") (pinfunction "6_6") (pintype "bidirectional"))
    )
    (net (code "75") (name "unconnected-(U$15-Pad7)") (class "Default")
      (node (ref "U$15") (pin "7") (pinfunction "7_7") (pintype "bidirectional"))
    )
    (net (code "76") (name "unconnected-(U$15-Pad8)") (class "Default")
      (node (ref "U$15") (pin "8") (pinfunction "8_8") (pintype "bidirectional"))
    )
    (net (code "77") (name "unconnected-(U$15-Pad9)") (class "Default")
      (node (ref "U$15") (pin "9") (pinfunction "9_9") (pintype "bidirectional"))
    )
    (net (code "78") (name "unconnected-(U1-PadAREF)") (class "Default")
      (node (ref "U1") (pin "AREF") (pinfunction "AREF_AREF") (pintype "bidirectional"))
    )
    (net (code "79") (name "unconnected-(U1-PadIOREF)") (class "Default")
      (node (ref "U1") (pin "IOREF") (pinfunction "IOREF_IOREF") (pintype "output"))
    )
    (net (code "80") (name "unconnected-(U1-PadRESERVED)") (class "Default")
      (node (ref "U1") (pin "RESERVED") (pinfunction "RESERVED_RESERVED") (pintype "no_connect"))
    )
  )
)
